# pc_healthypi_move_nRF5340_v2.net
KiCad netlist of a schematic drawn in EAGLE
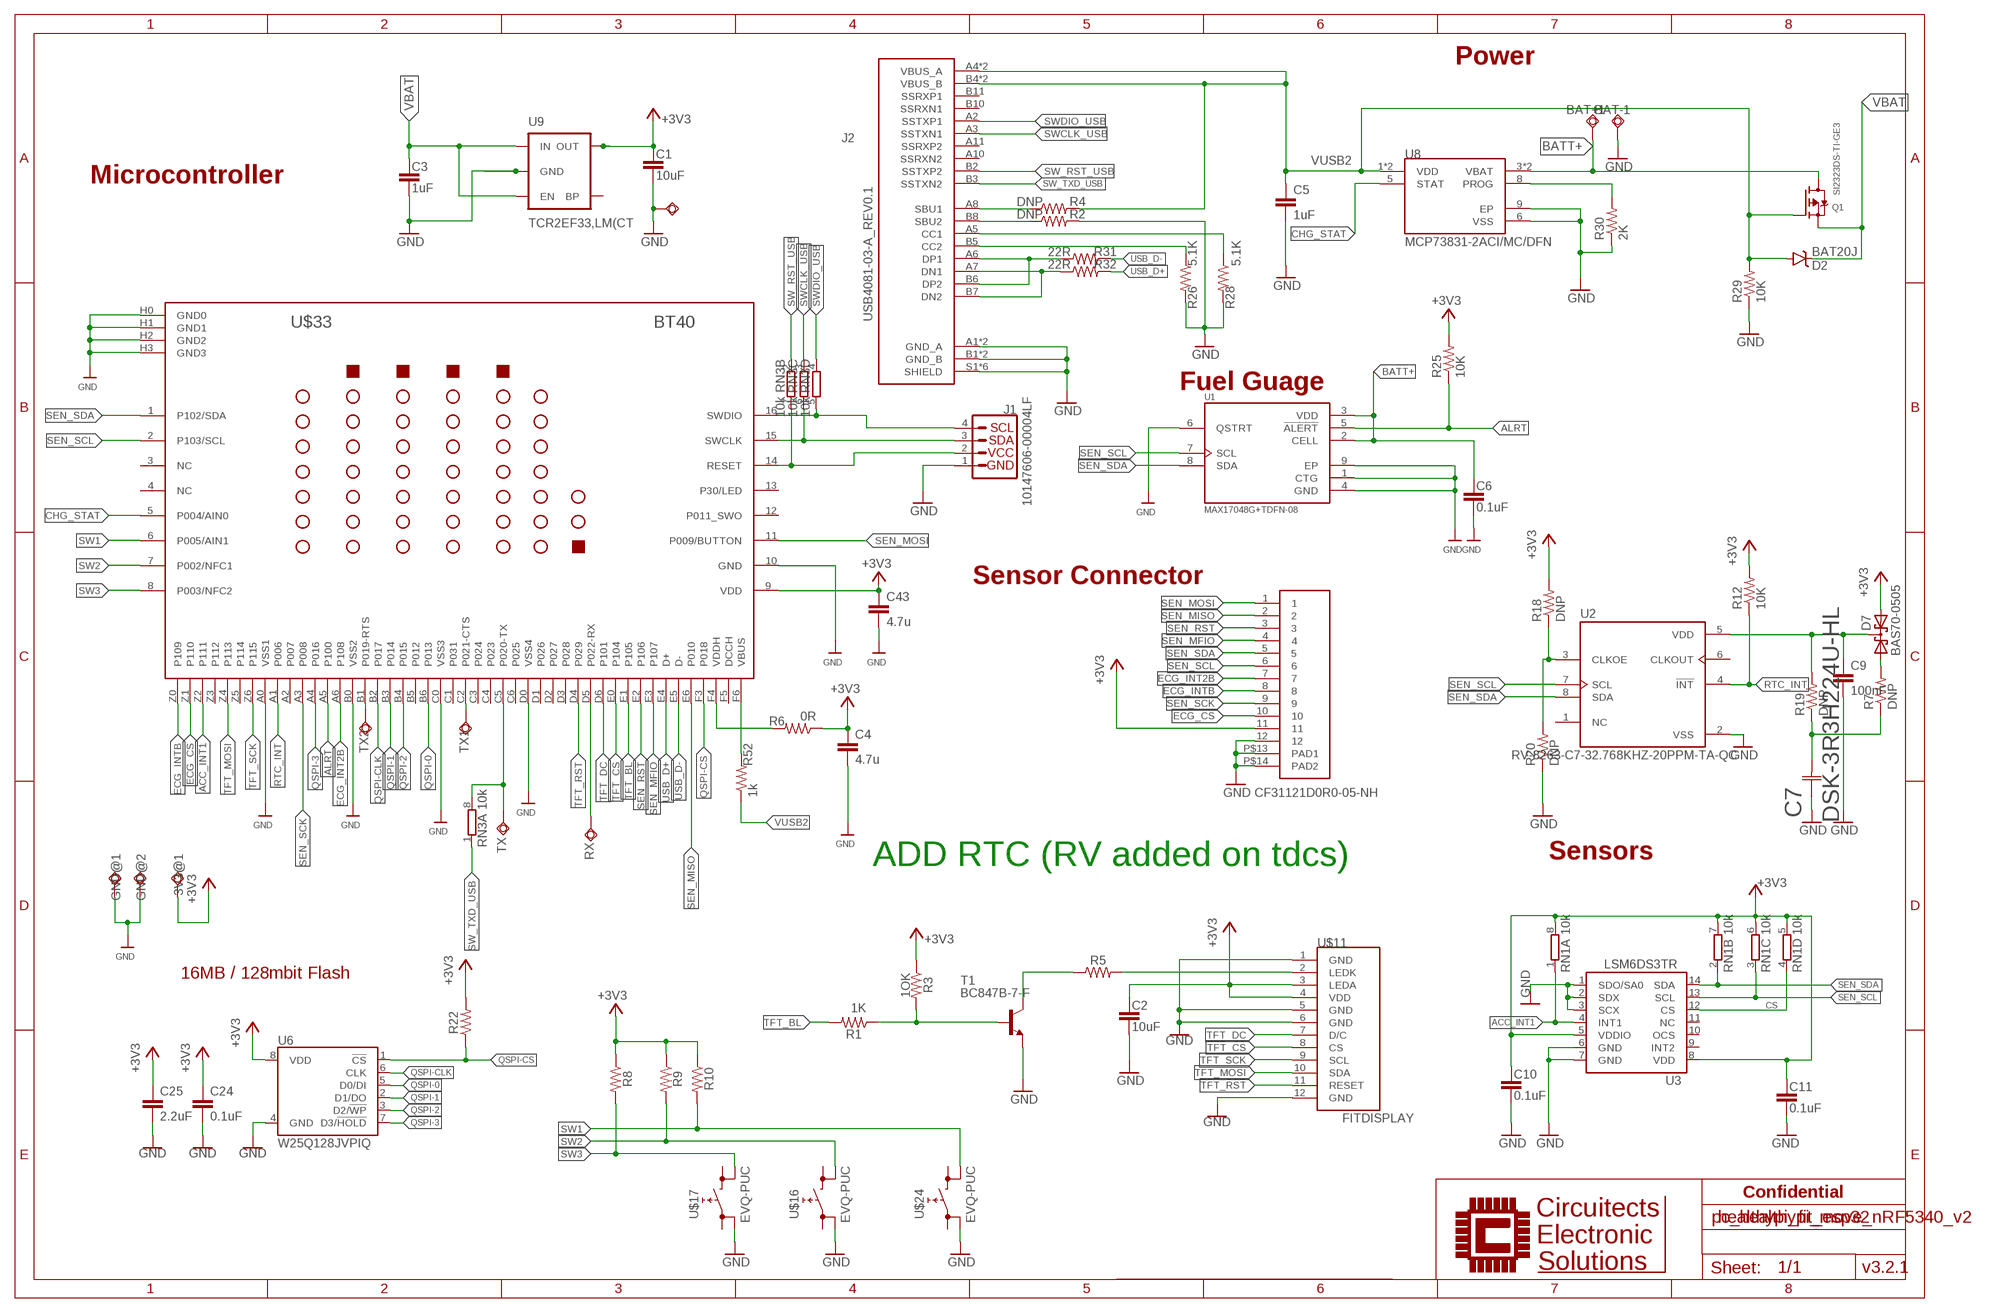
[diagram p0: schematic, sheet 1]

(export (version "E")
  (design (tool "Eeschema 10.0.6"))
  (components
    (comp (ref "3V3@1")
      (value "TPSQTP13SQ")
      (footprint "eagle-import:TP13SQ")
      (libsource (lib "eagle-import") (part "TPSQTP13SQ"))
    )
    (comp (ref "BAT+1")
      (value "TPSQTP13SQ")
      (footprint "eagle-import:TP13SQ")
      (libsource (lib "eagle-import") (part "TPSQTP13SQ"))
    )
    (comp (ref "BAT-1")
      (value "TPSQTP13SQ")
      (footprint "eagle-import:TP13SQ")
      (libsource (lib "eagle-import") (part "TPSQTP13SQ"))
    )
    (comp (ref "C1")
      (value "10uF")
      (footprint "eagle-import:0603@1")
      (libsource (lib "eagle-import") (part "0.1UF-0603-100V-10%"))
    )
    (comp (ref "C2")
      (value "10uF")
      (footprint "eagle-import:0603@1")
      (libsource (lib "eagle-import") (part "0.1UF-0603-100V-10%"))
    )
    (comp (ref "C3")
      (value "1uF")
      (footprint "eagle-import:0402-TIGHT")
      (libsource (lib "eagle-import") (part "0.1UF-0402T-6.3V-10%-X7R"))
    )
    (comp (ref "C4")
      (value "4.7u")
      (footprint "eagle-import:C0402")
      (libsource (lib "eagle-import") (part "C-EUC0402"))
    )
    (comp (ref "C5")
      (value "1uF")
      (footprint "eagle-import:0402-TIGHT")
      (libsource (lib "eagle-import") (part "2.2UF-0402_TIGHT-10V-10%-X5R"))
    )
    (comp (ref "C6")
      (value "0.1uF")
      (footprint "eagle-import:0402-TIGHT")
      (libsource (lib "eagle-import") (part "0.1UF-0402T-6.3V-10%-X7R"))
    )
    (comp (ref "C7")
      (value "DSK-3R3H224U-HL")
      (footprint "eagle-import:CAP_DSK-3R3H224U-HL_ELN")
      (fields (field (name "COPYRIGHT") "Copyright (C) 2023 Ultra Librarian. All rights reserved."))
      (libsource (lib "eagle-import") (part "DSK-3R3H224U-HL"))
    )
    (comp (ref "C9")
      (value "100nF")
      (footprint "eagle-import:C0402")
      (libsource (lib "eagle-import") (part "C-EUC0402"))
    )
    (comp (ref "C10")
      (value "0.1uF")
      (footprint "eagle-import:0402-TIGHT")
      (libsource (lib "eagle-import") (part "0.1UF-0402T-6.3V-10%-X7R"))
    )
    (comp (ref "C11")
      (value "0.1uF")
      (footprint "eagle-import:0402-TIGHT")
      (libsource (lib "eagle-import") (part "0.1UF-0402T-6.3V-10%-X7R"))
    )
    (comp (ref "C24")
      (value "0.1uF")
      (footprint "eagle-import:0402-TIGHT")
      (libsource (lib "eagle-import") (part "0.1UF-0402T-6.3V-10%-X7R"))
    )
    (comp (ref "C25")
      (value "2.2uF")
      (footprint "eagle-import:0402-TIGHT")
      (libsource (lib "eagle-import") (part "2.2UF-0402_TIGHT-10V-10%-X5R"))
    )
    (comp (ref "C43")
      (value "4.7u")
      (footprint "eagle-import:C0402")
      (libsource (lib "eagle-import") (part "C-EUC0402"))
    )
    (comp (ref "D2")
      (value "BAT20J")
      (footprint "eagle-import:SOD-323")
      (libsource (lib "eagle-import") (part "DIODE-SCHOTTKY-BAT20J"))
    )
    (comp (ref "D7")
      (value "BAS70-0505")
      (footprint "eagle-import:SOT23")
      (fields (field (name "MF") "Diotec") (field (name "MP") "BAS70-05"))
      (libsource (lib "eagle-import") (part "BAS70-0505"))
    )
    (comp (ref "GND@1")
      (value "TPSQTP13SQ")
      (footprint "eagle-import:TP13SQ")
      (libsource (lib "eagle-import") (part "TPSQTP13SQ"))
    )
    (comp (ref "GND@2")
      (value "TPSQTP13SQ")
      (footprint "eagle-import:TP13SQ")
      (libsource (lib "eagle-import") (part "TPSQTP13SQ"))
    )
    (comp (ref "J1")
      (value "10147606-00004LF")
      (footprint "eagle-import:JST04_1MM_RA")
      (libsource (lib "eagle-import") (part "QWIIC_CONNECTORJS-1MM"))
    )
    (comp (ref "J2")
      (value "USB4081-03-A_REV0.1")
      (footprint "eagle-import:GCT_USB4081-03-A_REV0.1")
      (fields (field (name "MF") "Global Connector Technology") (field (name "MP") "USB4081-03-A"))
      (libsource (lib "eagle-import") (part "USB4081-03-A_REV0.1"))
    )
    (comp (ref "Q1")
      (value "SI2323DS-TI-GE3")
      (footprint "eagle-import:SOT23-R")
      (libsource (lib "eagle-import") (part "MOSFET-P"))
    )
    (comp (ref "R1")
      (value "200")
      (footprint "eagle-import:R0402")
      (libsource (lib "eagle-import") (part "R-US_R0402"))
    )
    (comp (ref "R2")
      (value "DNP")
      (footprint "eagle-import:0402-RES")
      (libsource (lib "eagle-import") (part "RESISTOR0402-RES"))
    )
    (comp (ref "R3")
      (value "200")
      (footprint "eagle-import:R0402")
      (libsource (lib "eagle-import") (part "R-US_R0402"))
    )
    (comp (ref "R4")
      (value "DNP")
      (footprint "eagle-import:0402-RES")
      (libsource (lib "eagle-import") (part "RESISTOR0402-RES"))
    )
    (comp (ref "R5")
      (value "200R")
      (footprint "eagle-import:R0402")
      (libsource (lib "eagle-import") (part "R-US_R0402"))
    )
    (comp (ref "R6")
      (value "0R")
      (footprint "eagle-import:0402-RES")
      (libsource (lib "eagle-import") (part "RESISTOR0402-RES"))
    )
    (comp (ref "R7")
      (value "DNP")
      (footprint "eagle-import:R0402")
      (libsource (lib "eagle-import") (part "R-US_R0402"))
    )
    (comp (ref "R8")
      (value "200")
      (footprint "eagle-import:R0402")
      (libsource (lib "eagle-import") (part "R-US_R0402"))
    )
    (comp (ref "R9")
      (value "200")
      (footprint "eagle-import:R0402")
      (libsource (lib "eagle-import") (part "R-US_R0402"))
    )
    (comp (ref "R10")
      (value "200")
      (footprint "eagle-import:R0402")
      (libsource (lib "eagle-import") (part "R-US_R0402"))
    )
    (comp (ref "R12")
      (value "10K")
      (footprint "eagle-import:R0402")
      (libsource (lib "eagle-import") (part "R-US_R0402"))
    )
    (comp (ref "R18")
      (value "DNP")
      (footprint "eagle-import:R0402")
      (libsource (lib "eagle-import") (part "R-US_R0402"))
    )
    (comp (ref "R19")
      (value "DNP")
      (footprint "eagle-import:R0402")
      (libsource (lib "eagle-import") (part "R-US_R0402"))
    )
    (comp (ref "R20")
      (value "DNP")
      (footprint "eagle-import:R0402")
      (libsource (lib "eagle-import") (part "R-US_R0402"))
    )
    (comp (ref "R22")
      (value "10k")
      (footprint "eagle-import:R0402")
      (libsource (lib "eagle-import") (part "R-US_R0402"))
    )
    (comp (ref "R25")
      (value "10K")
      (footprint "eagle-import:0402-RES")
      (libsource (lib "eagle-import") (part "RESISTOR0402-RES"))
    )
    (comp (ref "R26")
      (value "5.1K")
      (footprint "eagle-import:0402-RES")
      (libsource (lib "eagle-import") (part "RESISTOR0402-RES"))
    )
    (comp (ref "R28")
      (value "5.1K")
      (footprint "eagle-import:0402-RES")
      (libsource (lib "eagle-import") (part "RESISTOR0402-RES"))
    )
    (comp (ref "R29")
      (value "10K")
      (footprint "eagle-import:R0402")
      (libsource (lib "eagle-import") (part "R-US_R0402"))
    )
    (comp (ref "R30")
      (value "2K")
      (footprint "eagle-import:R0402")
      (libsource (lib "eagle-import") (part "R-US_R0402"))
    )
    (comp (ref "R31")
      (value "22R")
      (footprint "eagle-import:0402-RES")
      (libsource (lib "eagle-import") (part "RESISTOR0402-RES"))
    )
    (comp (ref "R32")
      (value "22R")
      (footprint "eagle-import:0402-RES")
      (libsource (lib "eagle-import") (part "RESISTOR0402-RES"))
    )
    (comp (ref "R52")
      (value "1k")
      (footprint "eagle-import:0402-RES")
      (libsource (lib "eagle-import") (part "RESISTOR0402-RES"))
    )
    (comp (ref "RN1")
      (value "10k")
      (footprint "eagle-import:4X0402ARV341")
      (libsource (lib "eagle-import") (part "4R-N0402ARV341"))
    )
    (comp (ref "RN3")
      (value "10k")
      (footprint "eagle-import:4X0402ARV341")
      (libsource (lib "eagle-import") (part "4R-N0402ARV341"))
    )
    (comp (ref "RX")
      (value "TPSQTP13SQ")
      (footprint "eagle-import:TP13SQ")
      (libsource (lib "eagle-import") (part "TPSQTP13SQ"))
    )
    (comp (ref "SWIO6")
      (value "TPSQTP11R")
      (footprint "eagle-import:TP11R")
      (libsource (lib "eagle-import") (part "TPSQTP11R"))
    )
    (comp (ref "T1")
      (value "BC847B-7-F")
      (footprint "eagle-import:SOT23-BEC")
      (libsource (lib "eagle-import") (part "-NPN-SOT23-BECMMBT2222ALT1"))
    )
    (comp (ref "TX")
      (value "TPSQTP13SQ")
      (footprint "eagle-import:TP13SQ")
      (libsource (lib "eagle-import") (part "TPSQTP13SQ"))
    )
    (comp (ref "TX1")
      (value "TPSQTP13SQ")
      (footprint "eagle-import:TP13SQ")
      (libsource (lib "eagle-import") (part "TPSQTP13SQ"))
    )
    (comp (ref "TX2")
      (value "TPSQTP13SQ")
      (footprint "eagle-import:TP13SQ")
      (libsource (lib "eagle-import") (part "TPSQTP13SQ"))
    )
    (comp (ref "U$5")
      (value "CF31121D0R0-05-NH")
      (footprint "eagle-import:CF31121D0R0-05-NH")
      (libsource (lib "eagle-import") (part "CF31121D0R0-05-NH"))
    )
    (comp (ref "U$11")
      (value "FITDISPLAY")
      (footprint "eagle-import:FITDISPLAY")
      (libsource (lib "eagle-import") (part "FITDISPLAY"))
    )
    (comp (ref "U$16")
      (value "EVQ-PUC")
      (footprint "eagle-import:EVQ-PUC")
      (libsource (lib "eagle-import") (part "EVQ-PUC"))
    )
    (comp (ref "U$17")
      (value "EVQ-PUC")
      (footprint "eagle-import:EVQ-PUC")
      (libsource (lib "eagle-import") (part "EVQ-PUC"))
    )
    (comp (ref "U$24")
      (value "EVQ-PUC")
      (footprint "eagle-import:EVQ-PUC")
      (libsource (lib "eagle-import") (part "EVQ-PUC"))
    )
    (comp (ref "U$33")
      (value "BT40")
      (footprint "eagle-import:BT40")
      (libsource (lib "eagle-import") (part "BT40"))
    )
    (comp (ref "U1")
      (value "MAX17048G+TDFN-08")
      (footprint "eagle-import:SON50P200X200X80-9N")
      (fields (field (name "MF") "Analog Devices") (field (name "MP") "MAX17048G+"))
      (libsource (lib "eagle-import") (part "MAX17048G+TDFN-08"))
    )
    (comp (ref "U2")
      (value "RV-8263-C7-32.768KHZ-20PPM-TA-QC")
      (footprint "eagle-import:IC_RV-8263-C7-32.768KHZ-20PPM-TA-QC")
      (fields (field (name "MF") "Micro Crystal"))
      (libsource (lib "eagle-import") (part "RV-8263-C7-32.768KHZ-20PPM-TA-QC"))
    )
    (comp (ref "U3")
      (value "LSM6DS3TR")
      (footprint "eagle-import:LGA14L")
      (libsource (lib "eagle-import") (part "LSM6DS3"))
    )
    (comp (ref "U6")
      (value "W25Q128JVPIQ")
      (footprint "eagle-import:WSON-8-6X5-SKINNY_CENTERPAD")
      (libsource (lib "eagle-import") (part "W25QXX128MBIT-6X5-SKINNY_CENTER"))
    )
    (comp (ref "U8")
      (value "MCP73831-2ACI/MC/DFN")
      (footprint "eagle-import:SON50P200X300X100-9N")
      (fields (field (name "MF") "Microchip Technology") (field (name "MP") "MCP73831-2ACI/MC"))
      (libsource (lib "eagle-import") (part "MCP73831-2ACI/MC/DFN"))
    )
    (comp (ref "U9")
      (value "TCR2EF33,LM(CT")
      (footprint "eagle-import:SOT23-5")
      (libsource (lib "eagle-import") (part "V_REG_LDOSMD"))
    )
  )
  (nets
    (net (code "1") (name "+3V3") (class "Default")
      (node (ref "3V3@1") (pin "TP") (pinfunction "TP_TP") (pintype "input"))
      (node (ref "C1") (pin "1") (pinfunction "1_1") (pintype "passive"))
      (node (ref "C10") (pin "1") (pinfunction "1_1") (pintype "passive"))
      (node (ref "C11") (pin "1") (pinfunction "1_1") (pintype "passive"))
      (node (ref "C2") (pin "1") (pinfunction "1_1") (pintype "passive"))
      (node (ref "C24") (pin "1") (pinfunction "1_1") (pintype "passive"))
      (node (ref "C25") (pin "1") (pinfunction "1_1") (pintype "passive"))
      (node (ref "C4") (pin "1") (pinfunction "1_1") (pintype "passive"))
      (node (ref "C43") (pin "1") (pinfunction "1_1") (pintype "passive"))
      (node (ref "D7") (pin "2") (pinfunction "A2_2") (pintype "passive"))
      (node (ref "R10") (pin "1") (pinfunction "1_1") (pintype "passive"))
      (node (ref "R12") (pin "2") (pinfunction "2_2") (pintype "passive"))
      (node (ref "R18") (pin "2") (pinfunction "2_2") (pintype "passive"))
      (node (ref "R22") (pin "2") (pinfunction "2_2") (pintype "passive"))
      (node (ref "R25") (pin "2") (pinfunction "2_2") (pintype "passive"))
      (node (ref "R3") (pin "1") (pinfunction "1_1") (pintype "passive"))
      (node (ref "R6") (pin "1") (pinfunction "1_1") (pintype "passive"))
      (node (ref "R8") (pin "1") (pinfunction "1_1") (pintype "passive"))
      (node (ref "R9") (pin "1") (pinfunction "1_1") (pintype "passive"))
      (node (ref "RN1") (pin "5") (pinfunction "2_5") (pintype "passive"))
      (node (ref "RN1") (pin "6") (pinfunction "2_6") (pintype "passive"))
      (node (ref "RN1") (pin "7") (pinfunction "2_7") (pintype "passive"))
      (node (ref "RN1") (pin "8") (pinfunction "2_8") (pintype "passive"))
      (node (ref "U$11") (pin "3") (pinfunction "LEDA_3") (pintype "bidirectional"))
      (node (ref "U$11") (pin "4") (pinfunction "VDD_4") (pintype "bidirectional"))
      (node (ref "U$33") (pin "9") (pinfunction "VDD_9") (pintype "bidirectional"))
      (node (ref "U$5") (pin "11") (pinfunction "11_11") (pintype "bidirectional"))
      (node (ref "U3") (pin "5") (pinfunction "VDDIO_5") (pintype "bidirectional"))
      (node (ref "U3") (pin "8") (pinfunction "VDD_8") (pintype "bidirectional"))
      (node (ref "U6") (pin "8") (pinfunction "VDD_8") (pintype "bidirectional"))
      (node (ref "U9") (pin "5") (pinfunction "OUT_5") (pintype "passive"))
    )
    (net (code "2") (name "/CS") (class "Default")
      (node (ref "RN1") (pin "4") (pinfunction "1_4") (pintype "passive"))
      (node (ref "U3") (pin "12") (pinfunction "CS_12") (pintype "bidirectional"))
    )
    (net (code "3") (name "ACC_INT1") (class "Default")
      (node (ref "RN1") (pin "1") (pinfunction "1_1") (pintype "passive"))
      (node (ref "U$33") (pin "Z2") (pinfunction "P111_Z2") (pintype "bidirectional"))
      (node (ref "U3") (pin "4") (pinfunction "INT1_4") (pintype "bidirectional"))
    )
    (net (code "4") (name "ALRT") (class "Default")
      (node (ref "R25") (pin "1") (pinfunction "1_1") (pintype "passive"))
      (node (ref "U$33") (pin "A5") (pinfunction "P100_A5") (pintype "bidirectional"))
      (node (ref "U1") (pin "5") (pinfunction "~{ALERT}_5") (pintype "output"))
    )
    (net (code "5") (name "BATT+") (class "Default")
      (node (ref "BAT+1") (pin "TP") (pinfunction "TP_TP") (pintype "input"))
      (node (ref "C6") (pin "1") (pinfunction "1_1") (pintype "passive"))
      (node (ref "Q1") (pin "3") (pinfunction "D_3") (pintype "passive"))
      (node (ref "U1") (pin "2") (pinfunction "CELL_2") (pintype "power_in"))
      (node (ref "U1") (pin "3") (pinfunction "VDD_3") (pintype "power_in"))
      (node (ref "U8") (pin "3") (pinfunction "VBAT_3") (pintype "output"))
      (node (ref "U8") (pin "4") (pinfunction "VBAT_4") (pintype "output"))
    )
    (net (code "6") (name "CHG_STAT") (class "Default")
      (node (ref "U$33") (pin "5") (pinfunction "P004/AIN0_5") (pintype "bidirectional"))
      (node (ref "U8") (pin "5") (pinfunction "STAT_5") (pintype "output"))
    )
    (net (code "7") (name "ECG_CS") (class "Default")
      (node (ref "U$33") (pin "Z1") (pinfunction "P110_Z1") (pintype "bidirectional"))
      (node (ref "U$5") (pin "10") (pinfunction "10_10") (pintype "bidirectional"))
    )
    (net (code "8") (name "ECG_INT2B") (class "Default")
      (node (ref "U$33") (pin "A6") (pinfunction "P108_A6") (pintype "bidirectional"))
      (node (ref "U$5") (pin "7") (pinfunction "7_7") (pintype "bidirectional"))
    )
    (net (code "9") (name "ECG_INTB") (class "Default")
      (node (ref "U$33") (pin "Z0") (pinfunction "P109_Z0") (pintype "bidirectional"))
      (node (ref "U$5") (pin "8") (pinfunction "8_8") (pintype "bidirectional"))
    )
    (net (code "10") (name "GND") (class "Default")
      (node (ref "BAT-1") (pin "TP") (pinfunction "TP_TP") (pintype "input"))
      (node (ref "C1") (pin "2") (pinfunction "2_2") (pintype "passive"))
      (node (ref "C10") (pin "2") (pinfunction "2_2") (pintype "passive"))
      (node (ref "C11") (pin "2") (pinfunction "2_2") (pintype "passive"))
      (node (ref "C2") (pin "2") (pinfunction "2_2") (pintype "passive"))
      (node (ref "C24") (pin "2") (pinfunction "2_2") (pintype "passive"))
      (node (ref "C25") (pin "2") (pinfunction "2_2") (pintype "passive"))
      (node (ref "C3") (pin "2") (pinfunction "2_2") (pintype "passive"))
      (node (ref "C4") (pin "2") (pinfunction "2_2") (pintype "passive"))
      (node (ref "C43") (pin "2") (pinfunction "2_2") (pintype "passive"))
      (node (ref "C5") (pin "2") (pinfunction "2_2") (pintype "passive"))
      (node (ref "C6") (pin "2") (pinfunction "2_2") (pintype "passive"))
      (node (ref "C7") (pin "1") (pinfunction "1_1") (pintype "passive"))
      (node (ref "C9") (pin "2") (pinfunction "2_2") (pintype "passive"))
      (node (ref "GND@1") (pin "TP") (pinfunction "TP_TP") (pintype "input"))
      (node (ref "GND@2") (pin "TP") (pinfunction "TP_TP") (pintype "input"))
      (node (ref "J1") (pin "1") (pinfunction "1_1") (pintype "power_in"))
      (node (ref "J2") (pin "A1") (pinfunction "GND_A_A1") (pintype "power_in"))
      (node (ref "J2") (pin "A12") (pinfunction "GND_A_A12") (pintype "power_in"))
      (node (ref "J2") (pin "B1") (pinfunction "GND_B_B1") (pintype "power_in"))
      (node (ref "J2") (pin "B12") (pinfunction "GND_B_B12") (pintype "power_in"))
      (node (ref "J2") (pin "S1") (pinfunction "SHIELD_S1") (pintype "passive"))
      (node (ref "J2") (pin "S2") (pinfunction "SHIELD_S2") (pintype "passive"))
      (node (ref "J2") (pin "S3") (pinfunction "SHIELD_S3") (pintype "passive"))
      (node (ref "J2") (pin "S4") (pinfunction "SHIELD_S4") (pintype "passive"))
      (node (ref "J2") (pin "S5") (pinfunction "SHIELD_S5") (pintype "passive"))
      (node (ref "J2") (pin "S6") (pinfunction "SHIELD_S6") (pintype "passive"))
      (node (ref "R2") (pin "2") (pinfunction "2_2") (pintype "passive"))
      (node (ref "R20") (pin "1") (pinfunction "1_1") (pintype "passive"))
      (node (ref "R26") (pin "2") (pinfunction "2_2") (pintype "passive"))
      (node (ref "R28") (pin "2") (pinfunction "2_2") (pintype "passive"))
      (node (ref "R29") (pin "1") (pinfunction "1_1") (pintype "passive"))
      (node (ref "R30") (pin "1") (pinfunction "1_1") (pintype "passive"))
      (node (ref "SWIO6") (pin "TP") (pinfunction "TP_TP") (pintype "input"))
      (node (ref "T1") (pin "E") (pinfunction "E_E") (pintype "passive"))
      (node (ref "U$11") (pin "1") (pinfunction "GND_1") (pintype "bidirectional"))
      (node (ref "U$11") (pin "12") (pinfunction "GND_12") (pintype "bidirectional"))
      (node (ref "U$11") (pin "5") (pinfunction "GND_5") (pintype "bidirectional"))
      (node (ref "U$11") (pin "6") (pinfunction "GND_6") (pintype "bidirectional"))
      (node (ref "U$16") (pin "3") (pinfunction "0_3") (pintype "passive"))
      (node (ref "U$17") (pin "3") (pinfunction "0_3") (pintype "passive"))
      (node (ref "U$24") (pin "3") (pinfunction "0_3") (pintype "passive"))
      (node (ref "U$33") (pin "10") (pinfunction "GND_10") (pintype "bidirectional"))
      (node (ref "U$33") (pin "A0") (pinfunction "VSS1_A0") (pintype "bidirectional"))
      (node (ref "U$33") (pin "B0") (pinfunction "VSS2_B0") (pintype "bidirectional"))
      (node (ref "U$33") (pin "C0") (pinfunction "VSS3_C0") (pintype "bidirectional"))
      (node (ref "U$33") (pin "D0") (pinfunction "VSS4_D0") (pintype "bidirectional"))
      (node (ref "U$33") (pin "H0") (pinfunction "GND0_H0") (pintype "bidirectional"))
      (node (ref "U$33") (pin "H1") (pinfunction "GND1_H1") (pintype "bidirectional"))
      (node (ref "U$33") (pin "H2") (pinfunction "GND2_H2") (pintype "bidirectional"))
      (node (ref "U$33") (pin "H3") (pinfunction "GND3_H3") (pintype "bidirectional"))
      (node (ref "U$5") (pin "12") (pinfunction "12_12") (pintype "bidirectional"))
      (node (ref "U$5") (pin "P$13") (pinfunction "PAD1_P$13") (pintype "bidirectional"))
      (node (ref "U$5") (pin "P$14") (pinfunction "PAD2_P$14") (pintype "bidirectional"))
      (node (ref "U1") (pin "1") (pinfunction "CTG_1") (pintype "power_in"))
      (node (ref "U1") (pin "4") (pinfunction "GND_4") (pintype "power_in"))
      (node (ref "U1") (pin "6") (pinfunction "QSTRT_6") (pintype "input"))
      (node (ref "U1") (pin "9") (pinfunction "EP_9") (pintype "power_in"))
      (node (ref "U2") (pin "2") (pinfunction "VSS_2") (pintype "power_in"))
      (node (ref "U3") (pin "1") (pinfunction "SDO/SA0_1") (pintype "bidirectional"))
      (node (ref "U3") (pin "2") (pinfunction "SDX_2") (pintype "bidirectional"))
      (node (ref "U3") (pin "3") (pinfunction "SCX_3") (pintype "bidirectional"))
      (node (ref "U3") (pin "6") (pinfunction "GND_6") (pintype "bidirectional"))
      (node (ref "U3") (pin "7") (pinfunction "GND_7") (pintype "bidirectional"))
      (node (ref "U6") (pin "4") (pinfunction "GND_4") (pintype "bidirectional"))
      (node (ref "U8") (pin "6") (pinfunction "VSS_6") (pintype "power_in"))
      (node (ref "U8") (pin "9") (pinfunction "EP_9") (pintype "power_in"))
      (node (ref "U9") (pin "2") (pinfunction "GND_2") (pintype "input"))
    )
    (net (code "11") (name "Net-(C7-Pad2)") (class "Default")
      (node (ref "C7") (pin "2") (pinfunction "2_2") (pintype "passive"))
      (node (ref "R19") (pin "1") (pinfunction "1_1") (pintype "passive"))
      (node (ref "R7") (pin "1") (pinfunction "1_1") (pintype "passive"))
    )
    (net (code "12") (name "Net-(D7-A1)") (class "Default")
      (node (ref "D7") (pin "1") (pinfunction "A1_1") (pintype "passive"))
      (node (ref "R7") (pin "2") (pinfunction "2_2") (pintype "passive"))
    )
    (net (code "13") (name "Net-(D7-K1K2)") (class "Default")
      (node (ref "C9") (pin "1") (pinfunction "1_1") (pintype "passive"))
      (node (ref "D7") (pin "3") (pinfunction "K1K2_3") (pintype "passive"))
      (node (ref "R19") (pin "2") (pinfunction "2_2") (pintype "passive"))
      (node (ref "U2") (pin "5") (pinfunction "VDD_5") (pintype "power_in"))
    )
    (net (code "14") (name "Net-(J2-CC1)") (class "Default")
      (node (ref "J2") (pin "A5") (pinfunction "CC1_A5") (pintype "bidirectional"))
      (node (ref "R28") (pin "1") (pinfunction "1_1") (pintype "passive"))
    )
    (net (code "15") (name "Net-(J2-CC2)") (class "Default")
      (node (ref "J2") (pin "B5") (pinfunction "CC2_B5") (pintype "bidirectional"))
      (node (ref "R26") (pin "1") (pinfunction "1_1") (pintype "passive"))
    )
    (net (code "16") (name "Net-(J2-DN1)") (class "Default")
      (node (ref "J2") (pin "A7") (pinfunction "DN1_A7") (pintype "bidirectional"))
      (node (ref "J2") (pin "B7") (pinfunction "DN2_B7") (pintype "bidirectional"))
      (node (ref "R32") (pin "1") (pinfunction "1_1") (pintype "passive"))
    )
    (net (code "17") (name "Net-(J2-DP1)") (class "Default")
      (node (ref "J2") (pin "A6") (pinfunction "DP1_A6") (pintype "bidirectional"))
      (node (ref "J2") (pin "B6") (pinfunction "DP2_B6") (pintype "bidirectional"))
      (node (ref "R31") (pin "1") (pinfunction "1_1") (pintype "passive"))
    )
    (net (code "18") (name "Net-(J2-SBU1)") (class "Default")
      (node (ref "J2") (pin "A8") (pinfunction "SBU1_A8") (pintype "bidirectional"))
      (node (ref "R4") (pin "1") (pinfunction "1_1") (pintype "passive"))
    )
    (net (code "19") (name "Net-(J2-SBU2)") (class "Default")
      (node (ref "J2") (pin "B8") (pinfunction "SBU2_B8") (pintype "bidirectional"))
      (node (ref "R2") (pin "1") (pinfunction "1_1") (pintype "passive"))
    )
    (net (code "20") (name "Net-(R1-Pad1)") (class "Default")
      (node (ref "R1") (pin "1") (pinfunction "1_1") (pintype "passive"))
      (node (ref "R3") (pin "2") (pinfunction "2_2") (pintype "passive"))
      (node (ref "T1") (pin "B") (pinfunction "B_B") (pintype "passive"))
    )
    (net (code "21") (name "Net-(R5-Pad1)") (class "Default")
      (node (ref "R5") (pin "1") (pinfunction "1_1") (pintype "passive"))
      (node (ref "T1") (pin "C") (pinfunction "C_C") (pintype "passive"))
    )
    (net (code "22") (name "Net-(RN3A-2)") (class "Default")
      (node (ref "RN3") (pin "8") (pinfunction "2_8") (pintype "passive"))
      (node (ref "TX") (pin "TP") (pinfunction "TP_TP") (pintype "input"))
      (node (ref "U$33") (pin "C5") (pinfunction "P020-TX_C5") (pintype "bidirectional"))
    )
    (net (code "23") (name "Net-(RN3B-2)") (class "Default")
      (node (ref "J1") (pin "2") (pinfunction "2_2") (pintype "power_in"))
      (node (ref "RN3") (pin "7") (pinfunction "2_7") (pintype "passive"))
      (node (ref "U$33") (pin "14") (pinfunction "RESET_14") (pintype "bidirectional"))
    )
    (net (code "24") (name "Net-(RN3C-2)") (class "Default")
      (node (ref "J1") (pin "3") (pinfunction "3_3") (pintype "passive"))
      (node (ref "RN3") (pin "6") (pinfunction "2_6") (pintype "passive"))
      (node (ref "U$33") (pin "15") (pinfunction "SWCLK_15") (pintype "bidirectional"))
    )
    (net (code "25") (name "Net-(RN3D-2)") (class "Default")
      (node (ref "J1") (pin "4") (pinfunction "4_4") (pintype "passive"))
      (node (ref "RN3") (pin "5") (pinfunction "2_5") (pintype "passive"))
      (node (ref "U$33") (pin "16") (pinfunction "SWDIO_16") (pintype "bidirectional"))
    )
    (net (code "26") (name "Net-(U$11-LEDK)") (class "Default")
      (node (ref "R5") (pin "2") (pinfunction "2_2") (pintype "passive"))
      (node (ref "U$11") (pin "2") (pinfunction "LEDK_2") (pintype "bidirectional"))
    )
    (net (code "27") (name "Net-(U$33-P019-RTS)") (class "Default")
      (node (ref "TX2") (pin "TP") (pinfunction "TP_TP") (pintype "input"))
      (node (ref "U$33") (pin "B1") (pinfunction "P019-RTS_B1") (pintype "bidirectional"))
    )
    (net (code "28") (name "Net-(U$33-P021-CTS)") (class "Default")
      (node (ref "TX1") (pin "TP") (pinfunction "TP_TP") (pintype "input"))
      (node (ref "U$33") (pin "C2") (pinfunction "P021-CTS_C2") (pintype "bidirectional"))
    )
    (net (code "29") (name "Net-(U$33-P022-RX)") (class "Default")
      (node (ref "RX") (pin "TP") (pinfunction "TP_TP") (pintype "input"))
      (node (ref "U$33") (pin "D5") (pinfunction "P022-RX_D5") (pintype "bidirectional"))
    )
    (net (code "30") (name "Net-(U$33-VBUS)") (class "Default")
      (node (ref "R52") (pin "2") (pinfunction "2_2") (pintype "passive"))
      (node (ref "U$33") (pin "F6") (pinfunction "VBUS_F6") (pintype "bidirectional"))
    )
    (net (code "31") (name "Net-(U$33-VDDH)") (class "Default")
      (node (ref "R6") (pin "2") (pinfunction "2_2") (pintype "passive"))
      (node (ref "U$33") (pin "F4") (pinfunction "VDDH_F4") (pintype "bidirectional"))
    )
    (net (code "32") (name "Net-(U2-CLKOE)") (class "Default")
      (node (ref "R18") (pin "1") (pinfunction "1_1") (pintype "passive"))
      (node (ref "R20") (pin "2") (pinfunction "2_2") (pintype "passive"))
      (node (ref "U2") (pin "3") (pinfunction "CLKOE_3") (pintype "input"))
    )
    (net (code "33") (name "Net-(U8-PROG)") (class "Default")
      (node (ref "R30") (pin "2") (pinfunction "2_2") (pintype "passive"))
      (node (ref "U8") (pin "8") (pinfunction "PROG_8") (pintype "input"))
    )
    (net (code "34") (name "QSPI-0") (class "Default")
      (node (ref "U$33") (pin "B6") (pinfunction "P013_B6") (pintype "bidirectional"))
      (node (ref "U6") (pin "5") (pinfunction "D0/DI_5") (pintype "bidirectional"))
    )
    (net (code "35") (name "QSPI-1") (class "Default")
      (node (ref "U$33") (pin "B3") (pinfunction "P014_B3") (pintype "bidirectional"))
      (node (ref "U6") (pin "2") (pinfunction "D1/DO_2") (pintype "bidirectional"))
    )
    (net (code "36") (name "QSPI-2") (class "Default")
      (node (ref "U$33") (pin "B4") (pinfunction "P015_B4") (pintype "bidirectional"))
      (node (ref "U6") (pin "3") (pinfunction "D2/~{WP}_3") (pintype "bidirectional"))
    )
    (net (code "37") (name "QSPI-3") (class "Default")
      (node (ref "U$33") (pin "A4") (pinfunction "P016_A4") (pintype "bidirectional"))
      (node (ref "U6") (pin "7") (pinfunction "D3/~{HOLD}_7") (pintype "bidirectional"))
    )
    (net (code "38") (name "QSPI-CLK") (class "Default")
      (node (ref "U$33") (pin "B2") (pinfunction "P017_B2") (pintype "bidirectional"))
      (node (ref "U6") (pin "6") (pinfunction "CLK_6") (pintype "bidirectional"))
    )
    (net (code "39") (name "QSPI-CS") (class "Default")
      (node (ref "R22") (pin "1") (pinfunction "1_1") (pintype "passive"))
      (node (ref "U$33") (pin "F3") (pinfunction "P018_F3") (pintype "bidirectional"))
      (node (ref "U6") (pin "1") (pinfunction "~{CS}_1") (pintype "bidirectional"))
    )
    (net (code "40") (name "RTC_INT") (class "Default")
      (node (ref "R12") (pin "1") (pinfunction "1_1") (pintype "passive"))
      (node (ref "U$33") (pin "A1") (pinfunction "P006_A1") (pintype "bidirectional"))
      (node (ref "U2") (pin "4") (pinfunction "~{INT}_4") (pintype "output"))
    )
    (net (code "41") (name "SEN_MFIO") (class "Default")
      (node (ref "U$33") (pin "E3") (pinfunction "P107_E3") (pintype "bidirectional"))
      (node (ref "U$5") (pin "4") (pinfunction "4_4") (pintype "bidirectional"))
    )
    (net (code "42") (name "SEN_MISO") (class "Default")
      (node (ref "U$33") (pin "E6") (pinfunction "P010_E6") (pintype "bidirectional"))
      (node (ref "U$5") (pin "2") (pinfunction "2_2") (pintype "bidirectional"))
    )
    (net (code "43") (name "SEN_MOSI") (class "Default")
      (node (ref "U$33") (pin "11") (pinfunction "P009/BUTTON_11") (pintype "bidirectional"))
      (node (ref "U$5") (pin "1") (pinfunction "1_1") (pintype "bidirectional"))
    )
    (net (code "44") (name "SEN_RST") (class "Default")
      (node (ref "U$33") (pin "E2") (pinfunction "P106_E2") (pintype "bidirectional"))
      (node (ref "U$5") (pin "3") (pinfunction "3_3") (pintype "bidirectional"))
    )
    (net (code "45") (name "SEN_SCK") (class "Default")
      (node (ref "U$33") (pin "A3") (pinfunction "P008_A3") (pintype "bidirectional"))
      (node (ref "U$5") (pin "9") (pinfunction "9_9") (pintype "bidirectional"))
    )
    (net (code "46") (name "SEN_SCL") (class "Default")
      (node (ref "RN1") (pin "3") (pinfunction "1_3") (pintype "passive"))
      (node (ref "U$33") (pin "2") (pinfunction "P103/SCL_2") (pintype "bidirectional"))
      (node (ref "U$5") (pin "6") (pinfunction "6_6") (pintype "bidirectional"))
      (node (ref "U1") (pin "7") (pinfunction "SCL_7") (pintype "input"))
      (node (ref "U2") (pin "7") (pinfunction "SCL_7") (pintype "input"))
      (node (ref "U3") (pin "13") (pinfunction "SCL_13") (pintype "bidirectional"))
    )
    (net (code "47") (name "SEN_SDA") (class "Default")
      (node (ref "RN1") (pin "2") (pinfunction "1_2") (pintype "passive"))
      (node (ref "U$33") (pin "1") (pinfunction "P102/SDA_1") (pintype "bidirectional"))
      (node (ref "U$5") (pin "5") (pinfunction "5_5") (pintype "bidirectional"))
      (node (ref "U1") (pin "8") (pinfunction "SDA_8") (pintype "bidirectional"))
      (node (ref "U2") (pin "8") (pinfunction "SDA_8") (pintype "bidirectional"))
      (node (ref "U3") (pin "14") (pinfunction "SDA_14") (pintype "bidirectional"))
    )
    (net (code "48") (name "SW1") (class "Default")
      (node (ref "R10") (pin "2") (pinfunction "2_2") (pintype "passive"))
      (node (ref "U$24") (pin "2") (pinfunction "1_2") (pintype "passive"))
      (node (ref "U$33") (pin "6") (pinfunction "P005/AIN1_6") (pintype "bidirectional"))
    )
    (net (code "49") (name "SW2") (class "Default")
      (node (ref "R9") (pin "2") (pinfunction "2_2") (pintype "passive"))
      (node (ref "U$16") (pin "2") (pinfunction "1_2") (pintype "passive"))
      (node (ref "U$33") (pin "7") (pinfunction "P002/NFC1_7") (pintype "bidirectional"))
    )
    (net (code "50") (name "SW3") (class "Default")
      (node (ref "R8") (pin "2") (pinfunction "2_2") (pintype "passive"))
      (node (ref "U$17") (pin "2") (pinfunction "1_2") (pintype "passive"))
      (node (ref "U$33") (pin "8") (pinfunction "P003/NFC2_8") (pintype "bidirectional"))
    )
    (net (code "51") (name "SWCLK_USB") (class "Default")
      (node (ref "J2") (pin "A3") (pinfunction "SSTXN1_A3") (pintype "bidirectional"))
      (node (ref "RN3") (pin "3") (pinfunction "1_3") (pintype "passive"))
    )
    (net (code "52") (name "SWDIO_USB") (class "Default")
      (node (ref "J2") (pin "A2") (pinfunction "SSTXP1_A2") (pintype "bidirectional"))
      (node (ref "RN3") (pin "4") (pinfunction "1_4") (pintype "passive"))
    )
    (net (code "53") (name "SW_RST_USB") (class "Default")
      (node (ref "J2") (pin "B2") (pinfunction "SSTXP2_B2") (pintype "bidirectional"))
      (node (ref "RN3") (pin "2") (pinfunction "1_2") (pintype "passive"))
    )
    (net (code "54") (name "SW_TXD_USB") (class "Default")
      (node (ref "J2") (pin "B3") (pinfunction "SSTXN2_B3") (pintype "bidirectional"))
      (node (ref "RN3") (pin "1") (pinfunction "1_1") (pintype "passive"))
    )
    (net (code "55") (name "TFT_BL") (class "Default")
      (node (ref "R1") (pin "2") (pinfunction "2_2") (pintype "passive"))
      (node (ref "U$33") (pin "E1") (pinfunction "P105_E1") (pintype "bidirectional"))
    )
    (net (code "56") (name "TFT_CS") (class "Default")
      (node (ref "U$11") (pin "8") (pinfunction "CS_8") (pintype "bidirectional"))
      (node (ref "U$33") (pin "E0") (pinfunction "P104_E0") (pintype "bidirectional"))
    )
    (net (code "57") (name "TFT_DC") (class "Default")
      (node (ref "U$11") (pin "7") (pinfunction "D/C_7") (pintype "bidirectional"))
      (node (ref "U$33") (pin "D6") (pinfunction "P101_D6") (pintype "bidirectional"))
    )
    (net (code "58") (name "TFT_MOSI") (class "Default")
      (node (ref "U$11") (pin "10") (pinfunction "SDA_10") (pintype "bidirectional"))
      (node (ref "U$33") (pin "Z4") (pinfunction "P113_Z4") (pintype "bidirectional"))
    )
    (net (code "59") (name "TFT_RST") (class "Default")
      (node (ref "U$11") (pin "11") (pinfunction "RESET_11") (pintype "bidirectional"))
      (node (ref "U$33") (pin "D4") (pinfunction "P029_D4") (pintype "bidirectional"))
    )
    (net (code "60") (name "TFT_SCK") (class "Default")
      (node (ref "U$11") (pin "9") (pinfunction "SCL_9") (pintype "bidirectional"))
      (node (ref "U$33") (pin "Z6") (pinfunction "P115_Z6") (pintype "bidirectional"))
    )
    (net (code "61") (name "USB_D+") (class "Default")
      (node (ref "R32") (pin "2") (pinfunction "2_2") (pintype "passive"))
      (node (ref "U$33") (pin "E4") (pinfunction "D+_E4") (pintype "bidirectional"))
    )
    (net (code "62") (name "USB_D-") (class "Default")
      (node (ref "R31") (pin "2") (pinfunction "2_2") (pintype "passive"))
      (node (ref "U$33") (pin "E5") (pinfunction "D-_E5") (pintype "bidirectional"))
    )
    (net (code "63") (name "VBAT") (class "Default")
      (node (ref "C3") (pin "1") (pinfunction "1_1") (pintype "passive"))
      (node (ref "D2") (pin "C") (pinfunction "C_C") (pintype "passive"))
      (node (ref "Q1") (pin "2") (pinfunction "S_2") (pintype "passive"))
      (node (ref "U9") (pin "1") (pinfunction "IN_1") (pintype "input"))
      (node (ref "U9") (pin "3") (pinfunction "EN_3") (pintype "input"))
    )
    (net (code "64") (name "VUSB2") (class "Default")
      (node (ref "C5") (pin "1") (pinfunction "1_1") (pintype "passive"))
      (node (ref "D2") (pin "A") (pinfunction "A_A") (pintype "passive"))
      (node (ref "J2") (pin "A4") (pinfunction "VBUS_A_A4") (pintype "power_in"))
      (node (ref "J2") (pin "A9") (pinfunction "VBUS_A_A9") (pintype "power_in"))
      (node (ref "J2") (pin "B4") (pinfunction "VBUS_B_B4") (pintype "power_in"))
      (node (ref "J2") (pin "B9") (pinfunction "VBUS_B_B9") (pintype "power_in"))
      (node (ref "Q1") (pin "1") (pinfunction "G_1") (pintype "passive"))
      (node (ref "R29") (pin "2") (pinfunction "2_2") (pintype "passive"))
      (node (ref "R4") (pin "2") (pinfunction "2_2") (pintype "passive"))
      (node (ref "R52") (pin "1") (pinfunction "1_1") (pintype "passive"))
      (node (ref "U8") (pin "1") (pinfunction "VDD_1") (pintype "power_in"))
      (node (ref "U8") (pin "2") (pinfunction "VDD_2") (pintype "power_in"))
    )
    (net (code "65") (name "unconnected-(J2-SSRXN1-PadB10)") (class "Default")
      (node (ref "J2") (pin "B10") (pinfunction "SSRXN1_B10") (pintype "bidirectional"))
    )
    (net (code "66") (name "unconnected-(J2-SSRXN2-PadA10)") (class "Default")
      (node (ref "J2") (pin "A10") (pinfunction "SSRXN2_A10") (pintype "bidirectional"))
    )
    (net (code "67") (name "unconnected-(J2-SSRXP1-PadB11)") (class "Default")
      (node (ref "J2") (pin "B11") (pinfunction "SSRXP1_B11") (pintype "bidirectional"))
    )
    (net (code "68") (name "unconnected-(J2-SSRXP2-PadA11)") (class "Default")
      (node (ref "J2") (pin "A11") (pinfunction "SSRXP2_A11") (pintype "bidirectional"))
    )
    (net (code "69") (name "unconnected-(U$16-0-Pad1)") (class "Default")
      (node (ref "U$16") (pin "1") (pinfunction "0_1") (pintype "passive"))
    )
    (net (code "70") (name "unconnected-(U$16-1-Pad4)") (class "Default")
      (node (ref "U$16") (pin "4") (pinfunction "1_4") (pintype "passive"))
    )
    (net (code "71") (name "unconnected-(U$17-0-Pad1)") (class "Default")
      (node (ref "U$17") (pin "1") (pinfunction "0_1") (pintype "passive"))
    )
    (net (code "72") (name "unconnected-(U$17-1-Pad4)") (class "Default")
      (node (ref "U$17") (pin "4") (pinfunction "1_4") (pintype "passive"))
    )
    (net (code "73") (name "unconnected-(U$24-0-Pad1)") (class "Default")
      (node (ref "U$24") (pin "1") (pinfunction "0_1") (pintype "passive"))
    )
    (net (code "74") (name "unconnected-(U$24-1-Pad4)") (class "Default")
      (node (ref "U$24") (pin "4") (pinfunction "1_4") (pintype "passive"))
    )
    (net (code "75") (name "unconnected-(U$33-DCCH-PadF5)") (class "Default")
      (node (ref "U$33") (pin "F5") (pinfunction "DCCH_F5") (pintype "bidirectional"))
    )
    (net (code "76") (name "unconnected-(U$33-NC-Pad3)") (class "Default")
      (node (ref "U$33") (pin "3") (pinfunction "NC_3") (pintype "bidirectional"))
    )
    (net (code "77") (name "unconnected-(U$33-NC-Pad4)") (class "Default")
      (node (ref "U$33") (pin "4") (pinfunction "NC_4") (pintype "bidirectional"))
    )
    (net (code "78") (name "unconnected-(U$33-P007-PadA2)") (class "Default")
      (node (ref "U$33") (pin "A2") (pinfunction "P007_A2") (pintype "bidirectional"))
    )
    (net (code "79") (name "unconnected-(U$33-P011_SWO-Pad12)") (class "Default")
      (node (ref "U$33") (pin "12") (pinfunction "P011_SWO_12") (pintype "bidirectional"))
    )
    (net (code "80") (name "unconnected-(U$33-P012-PadB5)") (class "Default")
      (node (ref "U$33") (pin "B5") (pinfunction "P012_B5") (pintype "bidirectional"))
    )
    (net (code "81") (name "unconnected-(U$33-P023-PadC4)") (class "Default")
      (node (ref "U$33") (pin "C4") (pinfunction "P023_C4") (pintype "bidirectional"))
    )
    (net (code "82") (name "unconnected-(U$33-P024-PadC3)") (class "Default")
      (node (ref "U$33") (pin "C3") (pinfunction "P024_C3") (pintype "bidirectional"))
    )
    (net (code "83") (name "unconnected-(U$33-P025-PadC6)") (class "Default")
      (node (ref "U$33") (pin "C6") (pinfunction "P025_C6") (pintype "bidirectional"))
    )
    (net (code "84") (name "unconnected-(U$33-P026-PadD1)") (class "Default")
      (node (ref "U$33") (pin "D1") (pinfunction "P026_D1") (pintype "bidirectional"))
    )
    (net (code "85") (name "unconnected-(U$33-P027-PadD2)") (class "Default")
      (node (ref "U$33") (pin "D2") (pinfunction "P027_D2") (pintype "bidirectional"))
    )
    (net (code "86") (name "unconnected-(U$33-P028-PadD3)") (class "Default")
      (node (ref "U$33") (pin "D3") (pinfunction "P028_D3") (pintype "bidirectional"))
    )
    (net (code "87") (name "unconnected-(U$33-P30{slash}LED-Pad13)") (class "Default")
      (node (ref "U$33") (pin "13") (pinfunction "P30/LED_13") (pintype "bidirectional"))
    )
    (net (code "88") (name "unconnected-(U$33-P031-PadC1)") (class "Default")
      (node (ref "U$33") (pin "C1") (pinfunction "P031_C1") (pintype "bidirectional"))
    )
    (net (code "89") (name "unconnected-(U$33-P112-PadZ3)") (class "Default")
      (node (ref "U$33") (pin "Z3") (pinfunction "P112_Z3") (pintype "bidirectional"))
    )
    (net (code "90") (name "unconnected-(U$33-P114-PadZ5)") (class "Default")
      (node (ref "U$33") (pin "Z5") (pinfunction "P114_Z5") (pintype "bidirectional"))
    )
    (net (code "91") (name "unconnected-(U2-CLKOUT-Pad6)") (class "Default")
      (node (ref "U2") (pin "6") (pinfunction "CLKOUT_6") (pintype "output"))
    )
    (net (code "92") (name "unconnected-(U2-NC-Pad1)") (class "Default")
      (node (ref "U2") (pin "1") (pinfunction "NC_1") (pintype "no_connect"))
    )
    (net (code "93") (name "unconnected-(U3-INT2-Pad9)") (class "Default")
      (node (ref "U3") (pin "9") (pinfunction "INT2_9") (pintype "bidirectional"))
    )
    (net (code "94") (name "unconnected-(U3-NC-Pad11)") (class "Default")
      (node (ref "U3") (pin "11") (pinfunction "NC_11") (pintype "bidirectional"))
    )
    (net (code "95") (name "unconnected-(U3-OCS-Pad10)") (class "Default")
      (node (ref "U3") (pin "10") (pinfunction "OCS_10") (pintype "bidirectional"))
    )
    (net (code "96") (name "unconnected-(U9-BP-Pad4)") (class "Default")
      (node (ref "U9") (pin "4") (pinfunction "BP_4") (pintype "input"))
    )
  )
)
